# SDCard.net
KiCad netlist of a schematic drawn in Altium Designer
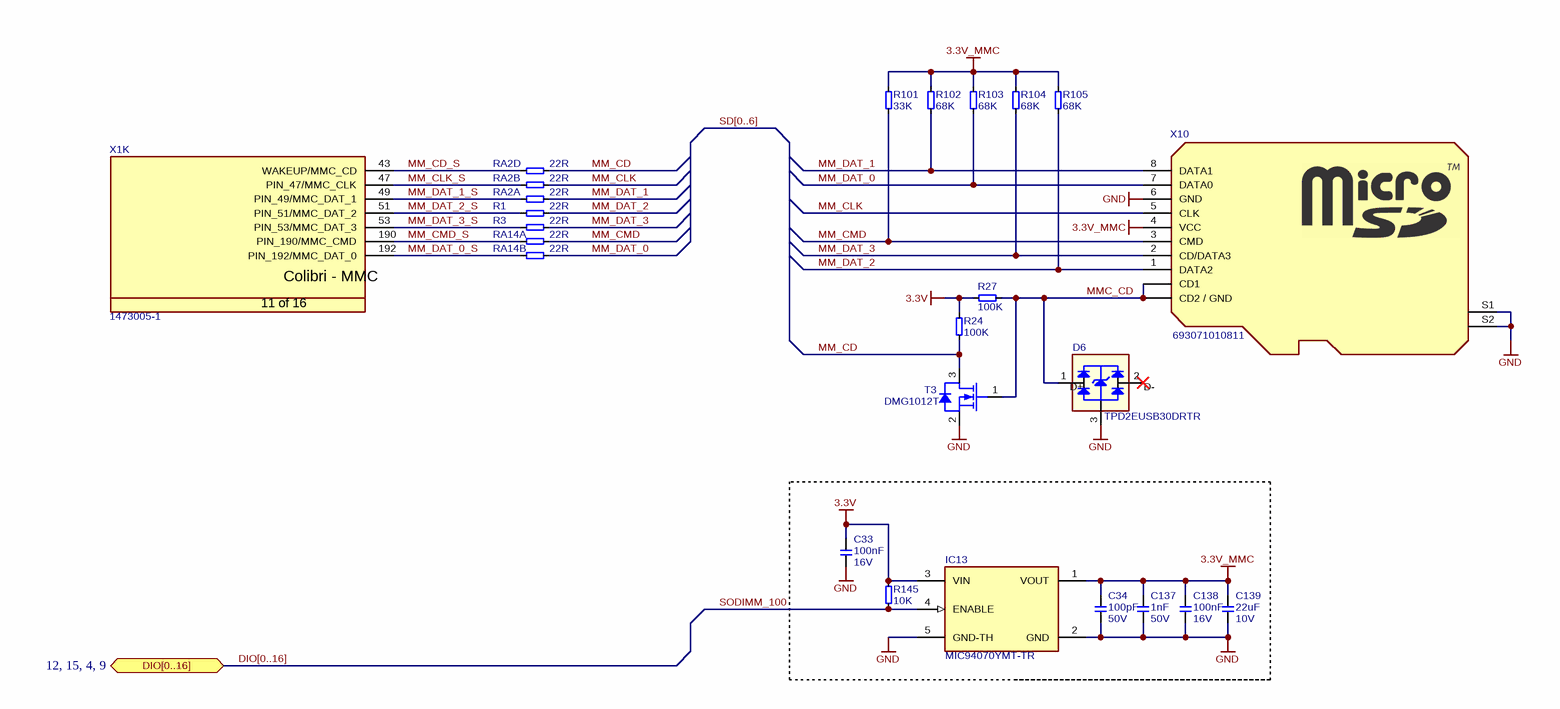
[diagram p0: SDCard.SchDoc]

(export (version "E")
  (design (tool "Eeschema 10.0.6"))
  (components
    (comp (ref "C33")
      (value "100nF")
      (footprint "CAPC1005X60N")
      (description "Capacitor Ceramic X7R 100nF 16V 10% 0402")
      (fields (field (name "TOLERANCE") "10%") (field (name "RATING") "16V"))
      (libsource (lib "Iris") (part "C-X7R-100nF-16V-10%-0402"))
    )
    (comp (ref "C34")
      (value "100pF")
      (footprint "CAPC1005X60N")
      (description "Capacitor Ceramic X7R 100pF 50V 10% 0402")
      (fields (field (name "TOLERANCE") "10%") (field (name "RATING") "50V"))
      (libsource (lib "Iris") (part "C-X7R-100pF-50V-10%-0402"))
    )
    (comp (ref "C137")
      (value "1nF")
      (footprint "CAPC1005X60N")
      (description "Capacitor Ceramic X7R 1nF 50V 10% 0402")
      (fields (field (name "TOLERANCE") "10%") (field (name "RATING") "50V"))
      (libsource (lib "Iris") (part "C-X7R-1nF-50V-10%-0402"))
    )
    (comp (ref "C138")
      (value "100nF")
      (footprint "CAPC1005X60N")
      (description "Capacitor Ceramic X7R 100nF 16V 10% 0402")
      (fields (field (name "TOLERANCE") "10%") (field (name "RATING") "16V"))
      (libsource (lib "Iris") (part "C-X7R-100nF-16V-10%-0402"))
    )
    (comp (ref "C139")
      (value "22uF")
      (footprint "T_CAPC0805X125N")
      (description "Capacitor Ceramic X5R 22uF 10V 20% 0805")
      (fields (field (name "TOLERANCE") "20%") (field (name "RATING") "10V"))
      (libsource (lib "Iris") (part "C-X5R-22uF-10V-20%-0805"))
    )
    (comp (ref "D6")
      (value "TPD2EUSB30DRTR")
      (footprint "T_TI_TPD2EUSB30DRTR")
      (description "2 Channel Protection for Super Speed USB3.0")
      (fields (field (name "MANUFACTURER PART NO.") "TPD2EUSB30DRTR"))
      (libsource (lib "Iris") (part "D-TI-TPD2EUSB30DRTR"))
    )
    (comp (ref "IC13")
      (value "MIC94070YMT-TR")
      (footprint "T_TDFN0P120X160X60-4N")
      (description "High Side Load Switch, TDFN4 1.2 x 1.6")
      (fields (field (name "MANUFACTURER PART NO.") "MIC94070YMT-TR"))
      (libsource (lib "Iris") (part "IC-Microchip-MIC94070YMT-TR"))
    )
    (comp (ref "R1")
      (value "22R")
      (footprint "RESC1005X40N")
      (description "Resistor 22 ohm 63mW 5% 0402")
      (fields (field (name "TOLERANCE") "5%"))
      (libsource (lib "Iris") (part "R-22R-63mW-5%-0402"))
    )
    (comp (ref "R3")
      (value "22R")
      (footprint "RESC1005X40N")
      (description "Resistor 22 ohm 63mW 5% 0402")
      (fields (field (name "TOLERANCE") "5%"))
      (libsource (lib "Iris") (part "R-22R-63mW-5%-0402"))
    )
    (comp (ref "R24")
      (value "100K")
      (footprint "T_RESC0603X30N")
      (description "Resistor 100 Kohm 63mW 5% 0603")
      (fields (field (name "TOLERANCE") "5%"))
      (libsource (lib "Iris") (part "R-100KR-63mW-5%-0603"))
    )
    (comp (ref "R27")
      (value "100K")
      (footprint "T_RESC0603X30N")
      (description "Resistor 100 Kohm 63mW 5% 0603")
      (fields (field (name "TOLERANCE") "5%"))
      (libsource (lib "Iris") (part "R-100KR-63mW-5%-0603"))
    )
    (comp (ref "R101")
      (value "33K")
      (footprint "RESC1005X40N")
      (description "Resistor 33 Kohm 63mW 5% 0402")
      (fields (field (name "TOLERANCE") "5%"))
      (libsource (lib "Iris") (part "R-33KR-63mW-5%-0402"))
    )
    (comp (ref "R102")
      (value "68K")
      (footprint "RESC1005X40N")
      (description "Resistor 68 Kohm 63mW 5% 0402")
      (fields (field (name "TOLERANCE") "5%"))
      (libsource (lib "Iris") (part "R-68KR-63mW-5%-0402"))
    )
    (comp (ref "R103")
      (value "68K")
      (footprint "RESC1005X40N")
      (description "Resistor 68 Kohm 63mW 5% 0402")
      (fields (field (name "TOLERANCE") "5%"))
      (libsource (lib "Iris") (part "R-68KR-63mW-5%-0402"))
    )
    (comp (ref "R104")
      (value "68K")
      (footprint "RESC1005X40N")
      (description "Resistor 68 Kohm 63mW 5% 0402")
      (fields (field (name "TOLERANCE") "5%"))
      (libsource (lib "Iris") (part "R-68KR-63mW-5%-0402"))
    )
    (comp (ref "R105")
      (value "68K")
      (footprint "RESC1005X40N")
      (description "Resistor 68 Kohm 63mW 5% 0402")
      (fields (field (name "TOLERANCE") "5%"))
      (libsource (lib "Iris") (part "R-68KR-63mW-5%-0402"))
    )
    (comp (ref "R145")
      (value "10K")
      (footprint "T_RESC0603X30N")
      (description "Resistor 10 Kohm 63mW 5% 0603")
      (fields (field (name "TOLERANCE") "5%"))
      (libsource (lib "Iris") (part "R-10KR-63mW-5%-0603"))
    )
    (comp (ref "RA2")
      (value "22R")
      (footprint "T_Resistor_Array_X4")
      (description "Resistor Array 22 R 63mW 5% 1206")
      (fields (field (name "TOLERANCE") "5%"))
      (libsource (lib "Iris") (part "RA-22R-63mW-5%-1206-div"))
    )
    (comp (ref "RA14")
      (value "22R")
      (footprint "T_Resistor_Array_X4")
      (description "Resistor Array 22 R 63mW 5% 1206")
      (fields (field (name "TOLERANCE") "5%"))
      (libsource (lib "Iris") (part "RA-22R-63mW-5%-1206-div"))
    )
    (comp (ref "T3")
      (value "T-DiodeInc-DMG1012T")
      (footprint "T_SOT50P160X80-3N")
      (description "N-Channel 20V (D-S)  MOSFET")
      (fields (field (name "MANUFACTURER PART NO.") "DMG1012T"))
      (libsource (lib "Iris") (part "T-DiodeInc-DMG1012T"))
    )
    (comp (ref "X1")
      (value "1473005-1")
      (footprint "T_Tyco_1473005-1")
      (description "SODIMM Connector")
      (fields (field (name "MANUFACTURER PART NO.") "1473005-1"))
      (libsource (lib "Iris") (part "CON-Tyco-1473005-1-200-0.6mm"))
    )
    (comp (ref "X10")
      (value "MicroSD Holder")
      (footprint "T_Wurth_693071010811")
      (description "Micro SD Holder Push Push CD")
      (fields (field (name "MANUFACTURER PART NO.") "693071010811"))
      (libsource (lib "Iris") (part "CON-Wurth-693071010811"))
    )
  )
  (nets
    (net (code "26") (name "/MMC_CD") (class "Default")
      (node (ref "D6") (pin "1") (pinfunction "D+_1") (pintype "power_in"))
      (node (ref "R27") (pin "1") (pinfunction "1_1") (pintype "passive"))
      (node (ref "T3") (pin "1") (pinfunction "G_1") (pintype "passive"))
      (node (ref "X10") (pin "CD1") (pinfunction "CD1_CD1") (pintype "power_in"))
      (node (ref "X10") (pin "CD2") (pinfunction "CD2_/_GND_CD2") (pintype "power_in"))
    )
    (net (code "27") (name "/MM_CD") (class "Default")
      (node (ref "R24") (pin "1") (pinfunction "1_1") (pintype "passive"))
      (node (ref "RA2") (pin "8") (pinfunction "8_8") (pintype "passive"))
      (node (ref "T3") (pin "3") (pinfunction "D_3") (pintype "passive"))
    )
    (net (code "28") (name "/MM_CD_S") (class "Default")
      (node (ref "RA2") (pin "4") (pinfunction "4_4") (pintype "passive"))
      (node (ref "X1") (pin "43") (pinfunction "WAKEUP/MMC_CD_43") (pintype "passive"))
    )
    (net (code "29") (name "/MM_CLK") (class "Default")
      (node (ref "RA2") (pin "6") (pinfunction "6_6") (pintype "passive"))
      (node (ref "X10") (pin "5") (pinfunction "CLK_5") (pintype "power_in"))
    )
    (net (code "30") (name "/MM_CLK_S") (class "Default")
      (node (ref "RA2") (pin "2") (pinfunction "2_2") (pintype "passive"))
      (node (ref "X1") (pin "47") (pinfunction "PIN_47/MMC_CLK_47") (pintype "passive"))
    )
    (net (code "31") (name "/MM_CMD") (class "Default")
      (node (ref "R101") (pin "1") (pinfunction "1_1") (pintype "passive"))
      (node (ref "RA14") (pin "5") (pinfunction "5_5") (pintype "passive"))
      (node (ref "X10") (pin "3") (pinfunction "CMD_3") (pintype "passive"))
    )
    (net (code "32") (name "/MM_CMD_S") (class "Default")
      (node (ref "RA14") (pin "1") (pinfunction "1_1") (pintype "passive"))
      (node (ref "X1") (pin "190") (pinfunction "PIN_190/MMC_CMD_190") (pintype "passive"))
    )
    (net (code "33") (name "/MM_DAT_0") (class "Default")
      (node (ref "R103") (pin "1") (pinfunction "1_1") (pintype "passive"))
      (node (ref "RA14") (pin "6") (pinfunction "6_6") (pintype "passive"))
      (node (ref "X10") (pin "7") (pinfunction "DATA0_7") (pintype "power_in"))
    )
    (net (code "34") (name "/MM_DAT_0_S") (class "Default")
      (node (ref "RA14") (pin "2") (pinfunction "2_2") (pintype "passive"))
      (node (ref "X1") (pin "192") (pinfunction "PIN_192/MMC_DAT_0_192") (pintype "passive"))
    )
    (net (code "35") (name "/MM_DAT_1") (class "Default")
      (node (ref "R102") (pin "1") (pinfunction "1_1") (pintype "passive"))
      (node (ref "RA2") (pin "5") (pinfunction "5_5") (pintype "passive"))
      (node (ref "X10") (pin "8") (pinfunction "DATA1_8") (pintype "power_in"))
    )
    (net (code "36") (name "/MM_DAT_1_S") (class "Default")
      (node (ref "RA2") (pin "1") (pinfunction "1_1") (pintype "passive"))
      (node (ref "X1") (pin "49") (pinfunction "PIN_49/MMC_DAT_1_49") (pintype "passive"))
    )
    (net (code "37") (name "/MM_DAT_2") (class "Default")
      (node (ref "R1") (pin "2") (pinfunction "2_2") (pintype "passive"))
      (node (ref "R105") (pin "1") (pinfunction "1_1") (pintype "passive"))
      (node (ref "X10") (pin "1") (pinfunction "DATA2_1") (pintype "power_in"))
    )
    (net (code "38") (name "/MM_DAT_2_S") (class "Default")
      (node (ref "R1") (pin "1") (pinfunction "1_1") (pintype "passive"))
      (node (ref "X1") (pin "51") (pinfunction "PIN_51/MMC_DAT_2_51") (pintype "passive"))
    )
    (net (code "39") (name "/MM_DAT_3") (class "Default")
      (node (ref "R104") (pin "1") (pinfunction "1_1") (pintype "passive"))
      (node (ref "R3") (pin "2") (pinfunction "2_2") (pintype "passive"))
      (node (ref "X10") (pin "2") (pinfunction "CD/DATA3_2") (pintype "passive"))
    )
    (net (code "40") (name "/MM_DAT_3_S") (class "Default")
      (node (ref "R3") (pin "1") (pinfunction "1_1") (pintype "passive"))
      (node (ref "X1") (pin "53") (pinfunction "PIN_53/MMC_DAT_3_53") (pintype "passive"))
    )
    (net (code "42") (name "/SODIMM_100") (class "Default")
      (node (ref "IC13") (pin "4") (pinfunction "ENABLE_4") (pintype "input"))
      (node (ref "R145") (pin "1") (pinfunction "1_1") (pintype "passive"))
    )
    (net (code "43") (name "3.3V") (class "Default")
      (node (ref "C33") (pin "2") (pinfunction "2_2") (pintype "passive"))
      (node (ref "IC13") (pin "3") (pinfunction "VIN_3") (pintype "power_in"))
      (node (ref "R145") (pin "2") (pinfunction "2_2") (pintype "passive"))
      (node (ref "R24") (pin "2") (pinfunction "2_2") (pintype "passive"))
      (node (ref "R27") (pin "2") (pinfunction "2_2") (pintype "passive"))
    )
    (net (code "44") (name "3.3V_MMC") (class "Default")
      (node (ref "C137") (pin "2") (pinfunction "2_2") (pintype "passive"))
      (node (ref "C138") (pin "2") (pinfunction "2_2") (pintype "passive"))
      (node (ref "C139") (pin "2") (pinfunction "2_2") (pintype "passive"))
      (node (ref "C34") (pin "2") (pinfunction "2_2") (pintype "passive"))
      (node (ref "IC13") (pin "1") (pinfunction "VOUT_1") (pintype "power_in"))
      (node (ref "R101") (pin "2") (pinfunction "2_2") (pintype "passive"))
      (node (ref "R102") (pin "2") (pinfunction "2_2") (pintype "passive"))
      (node (ref "R103") (pin "2") (pinfunction "2_2") (pintype "passive"))
      (node (ref "R104") (pin "2") (pinfunction "2_2") (pintype "passive"))
      (node (ref "R105") (pin "2") (pinfunction "2_2") (pintype "passive"))
      (node (ref "X10") (pin "4") (pinfunction "VCC_4") (pintype "passive"))
    )
    (net (code "45") (name "GND") (class "Default")
      (node (ref "C137") (pin "1") (pinfunction "1_1") (pintype "passive"))
      (node (ref "C138") (pin "1") (pinfunction "1_1") (pintype "passive"))
      (node (ref "C139") (pin "1") (pinfunction "1_1") (pintype "passive"))
      (node (ref "C33") (pin "1") (pinfunction "1_1") (pintype "passive"))
      (node (ref "C34") (pin "1") (pinfunction "1_1") (pintype "passive"))
      (node (ref "D6") (pin "3") (pinfunction "3_3") (pintype "power_in"))
      (node (ref "IC13") (pin "2") (pinfunction "GND_2") (pintype "power_in"))
      (node (ref "IC13") (pin "5") (pinfunction "GND-TH_5") (pintype "power_in"))
      (node (ref "T3") (pin "2") (pinfunction "S_2") (pintype "passive"))
      (node (ref "X10") (pin "6") (pinfunction "GND_6") (pintype "power_in"))
      (node (ref "X10") (pin "S1") (pinfunction "S_S1") (pintype "passive"))
      (node (ref "X10") (pin "S2") (pinfunction "S_S2") (pintype "passive"))
    )
    (net (code "46") (name "unconnected-(D6-D--Pad2)") (class "Default")
      (node (ref "D6") (pin "2") (pinfunction "D-_2") (pintype "power_in+no_connect"))
    )
  )
)
